# SCH_Record-wav_2025-12-09.net
KiCad netlist of a schematic drawn in EasyEDA
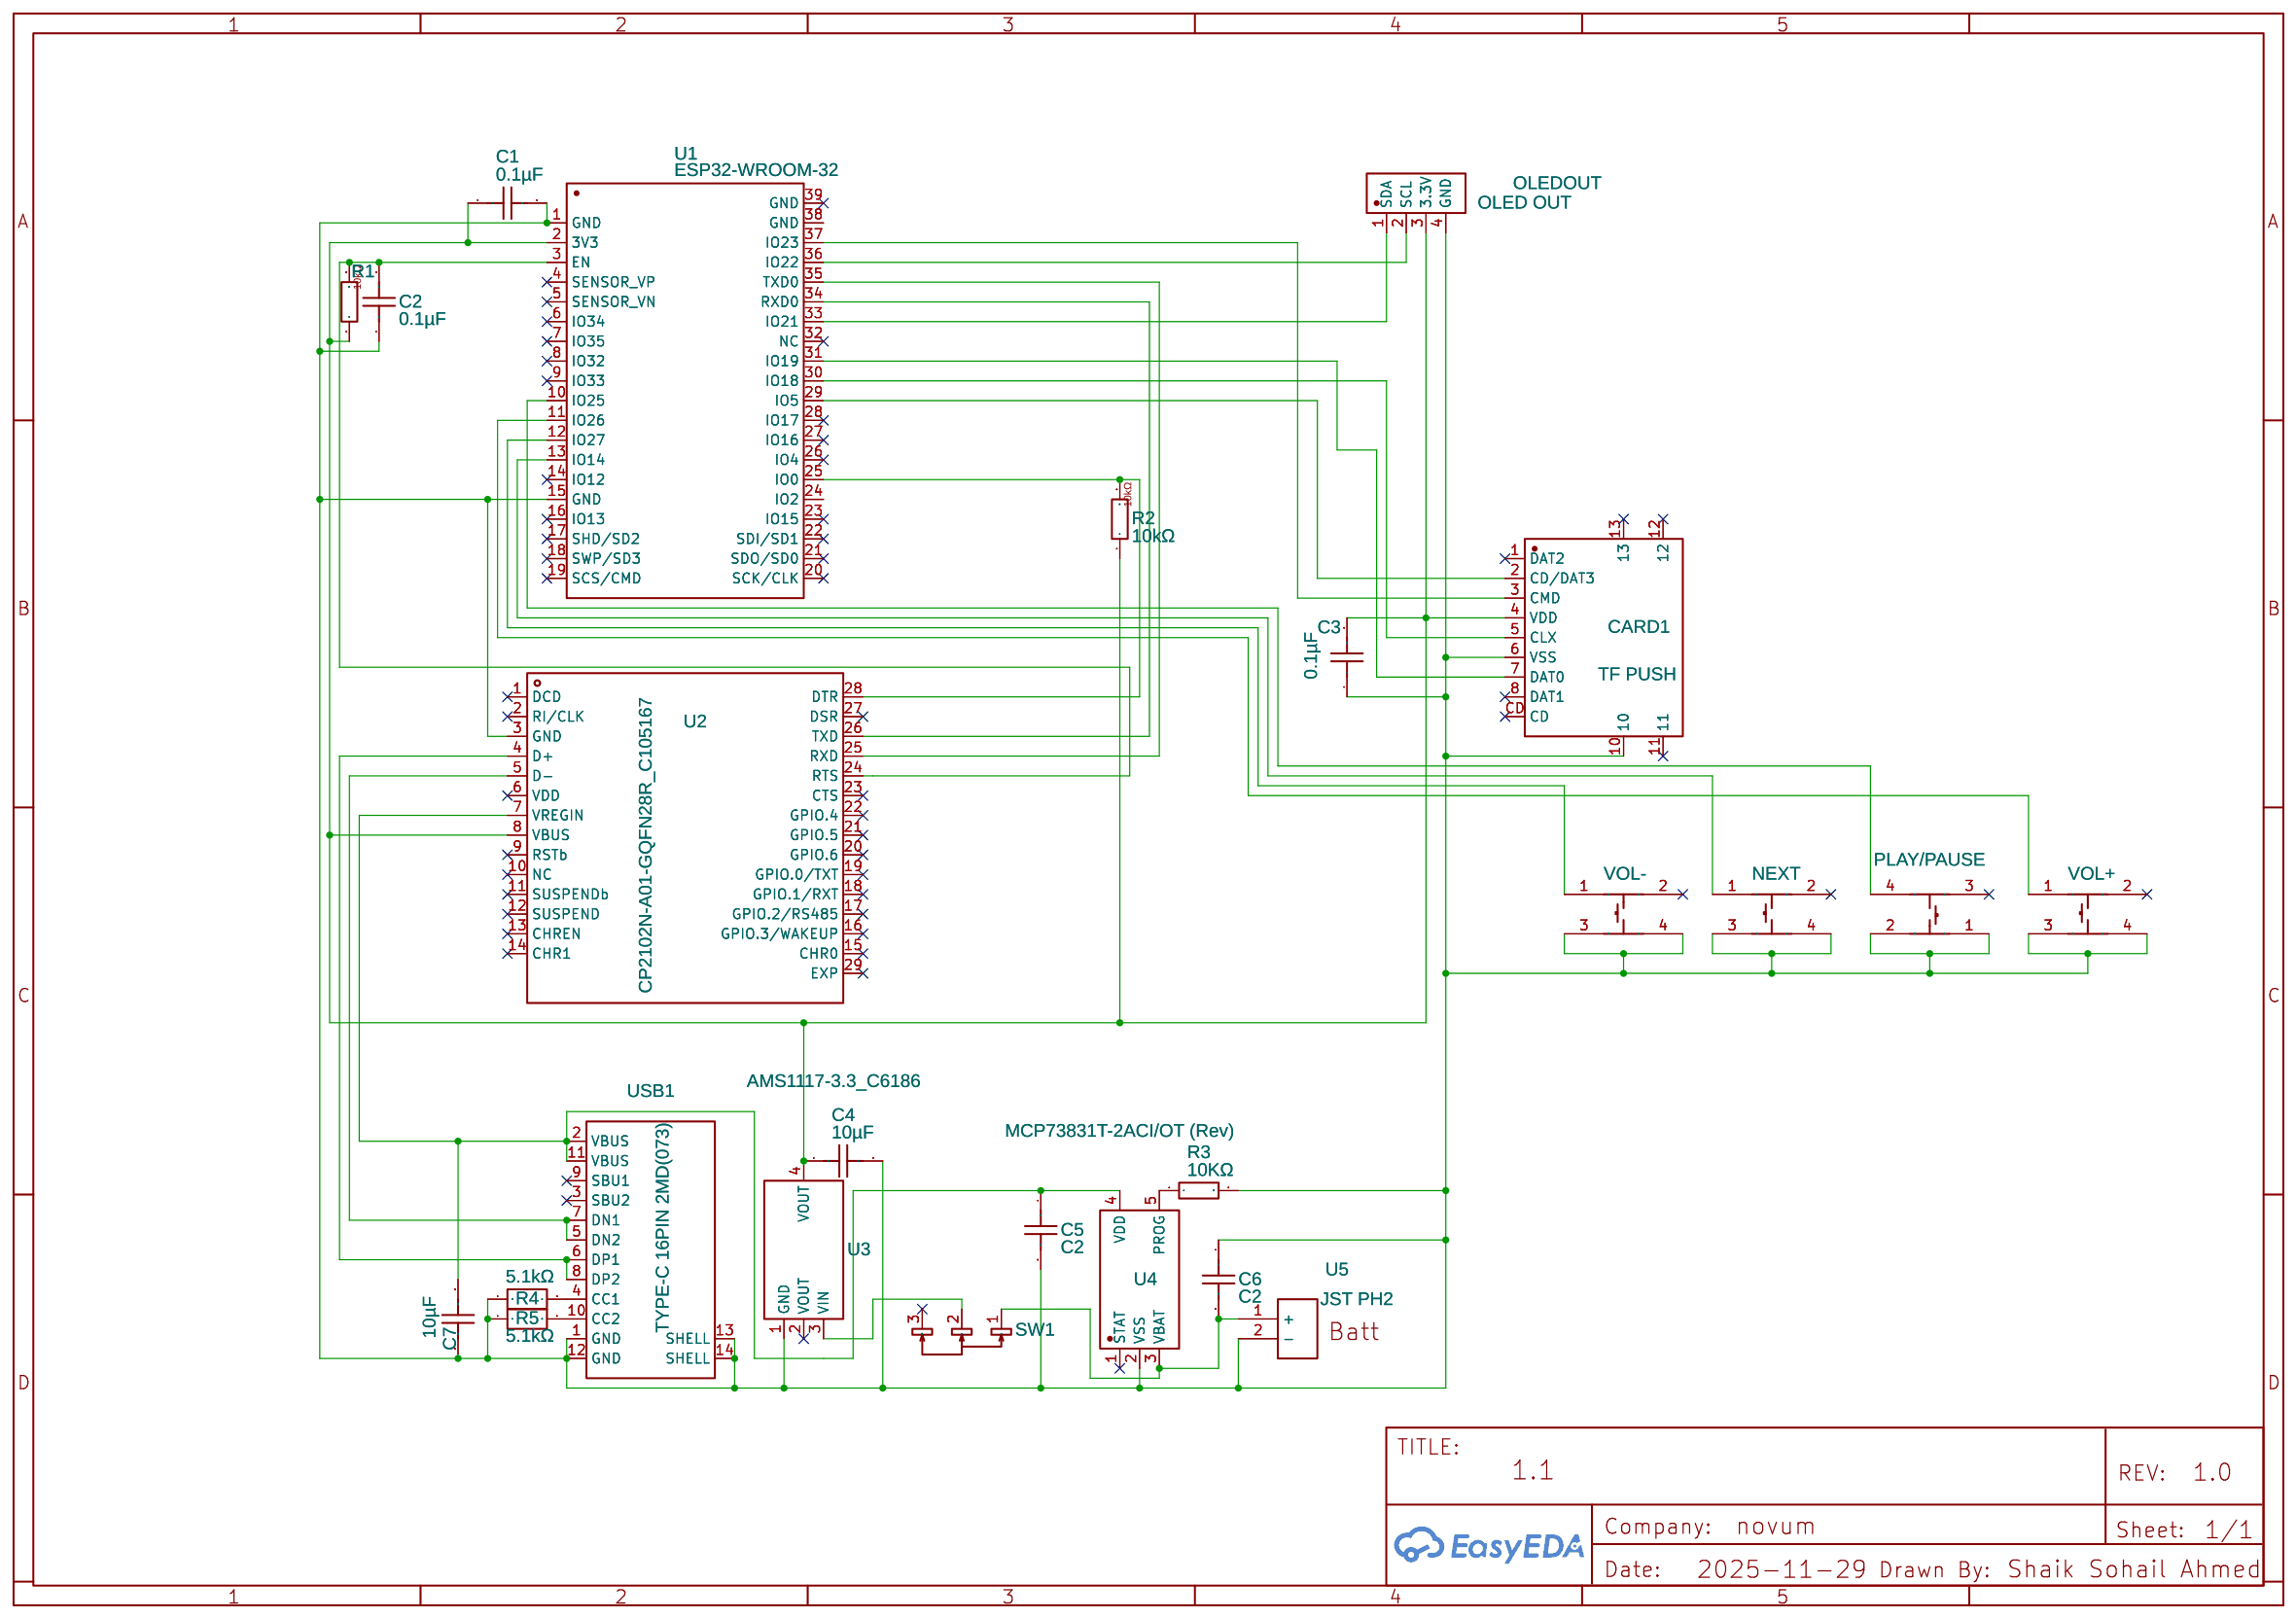
[diagram p0: Sheet_1]
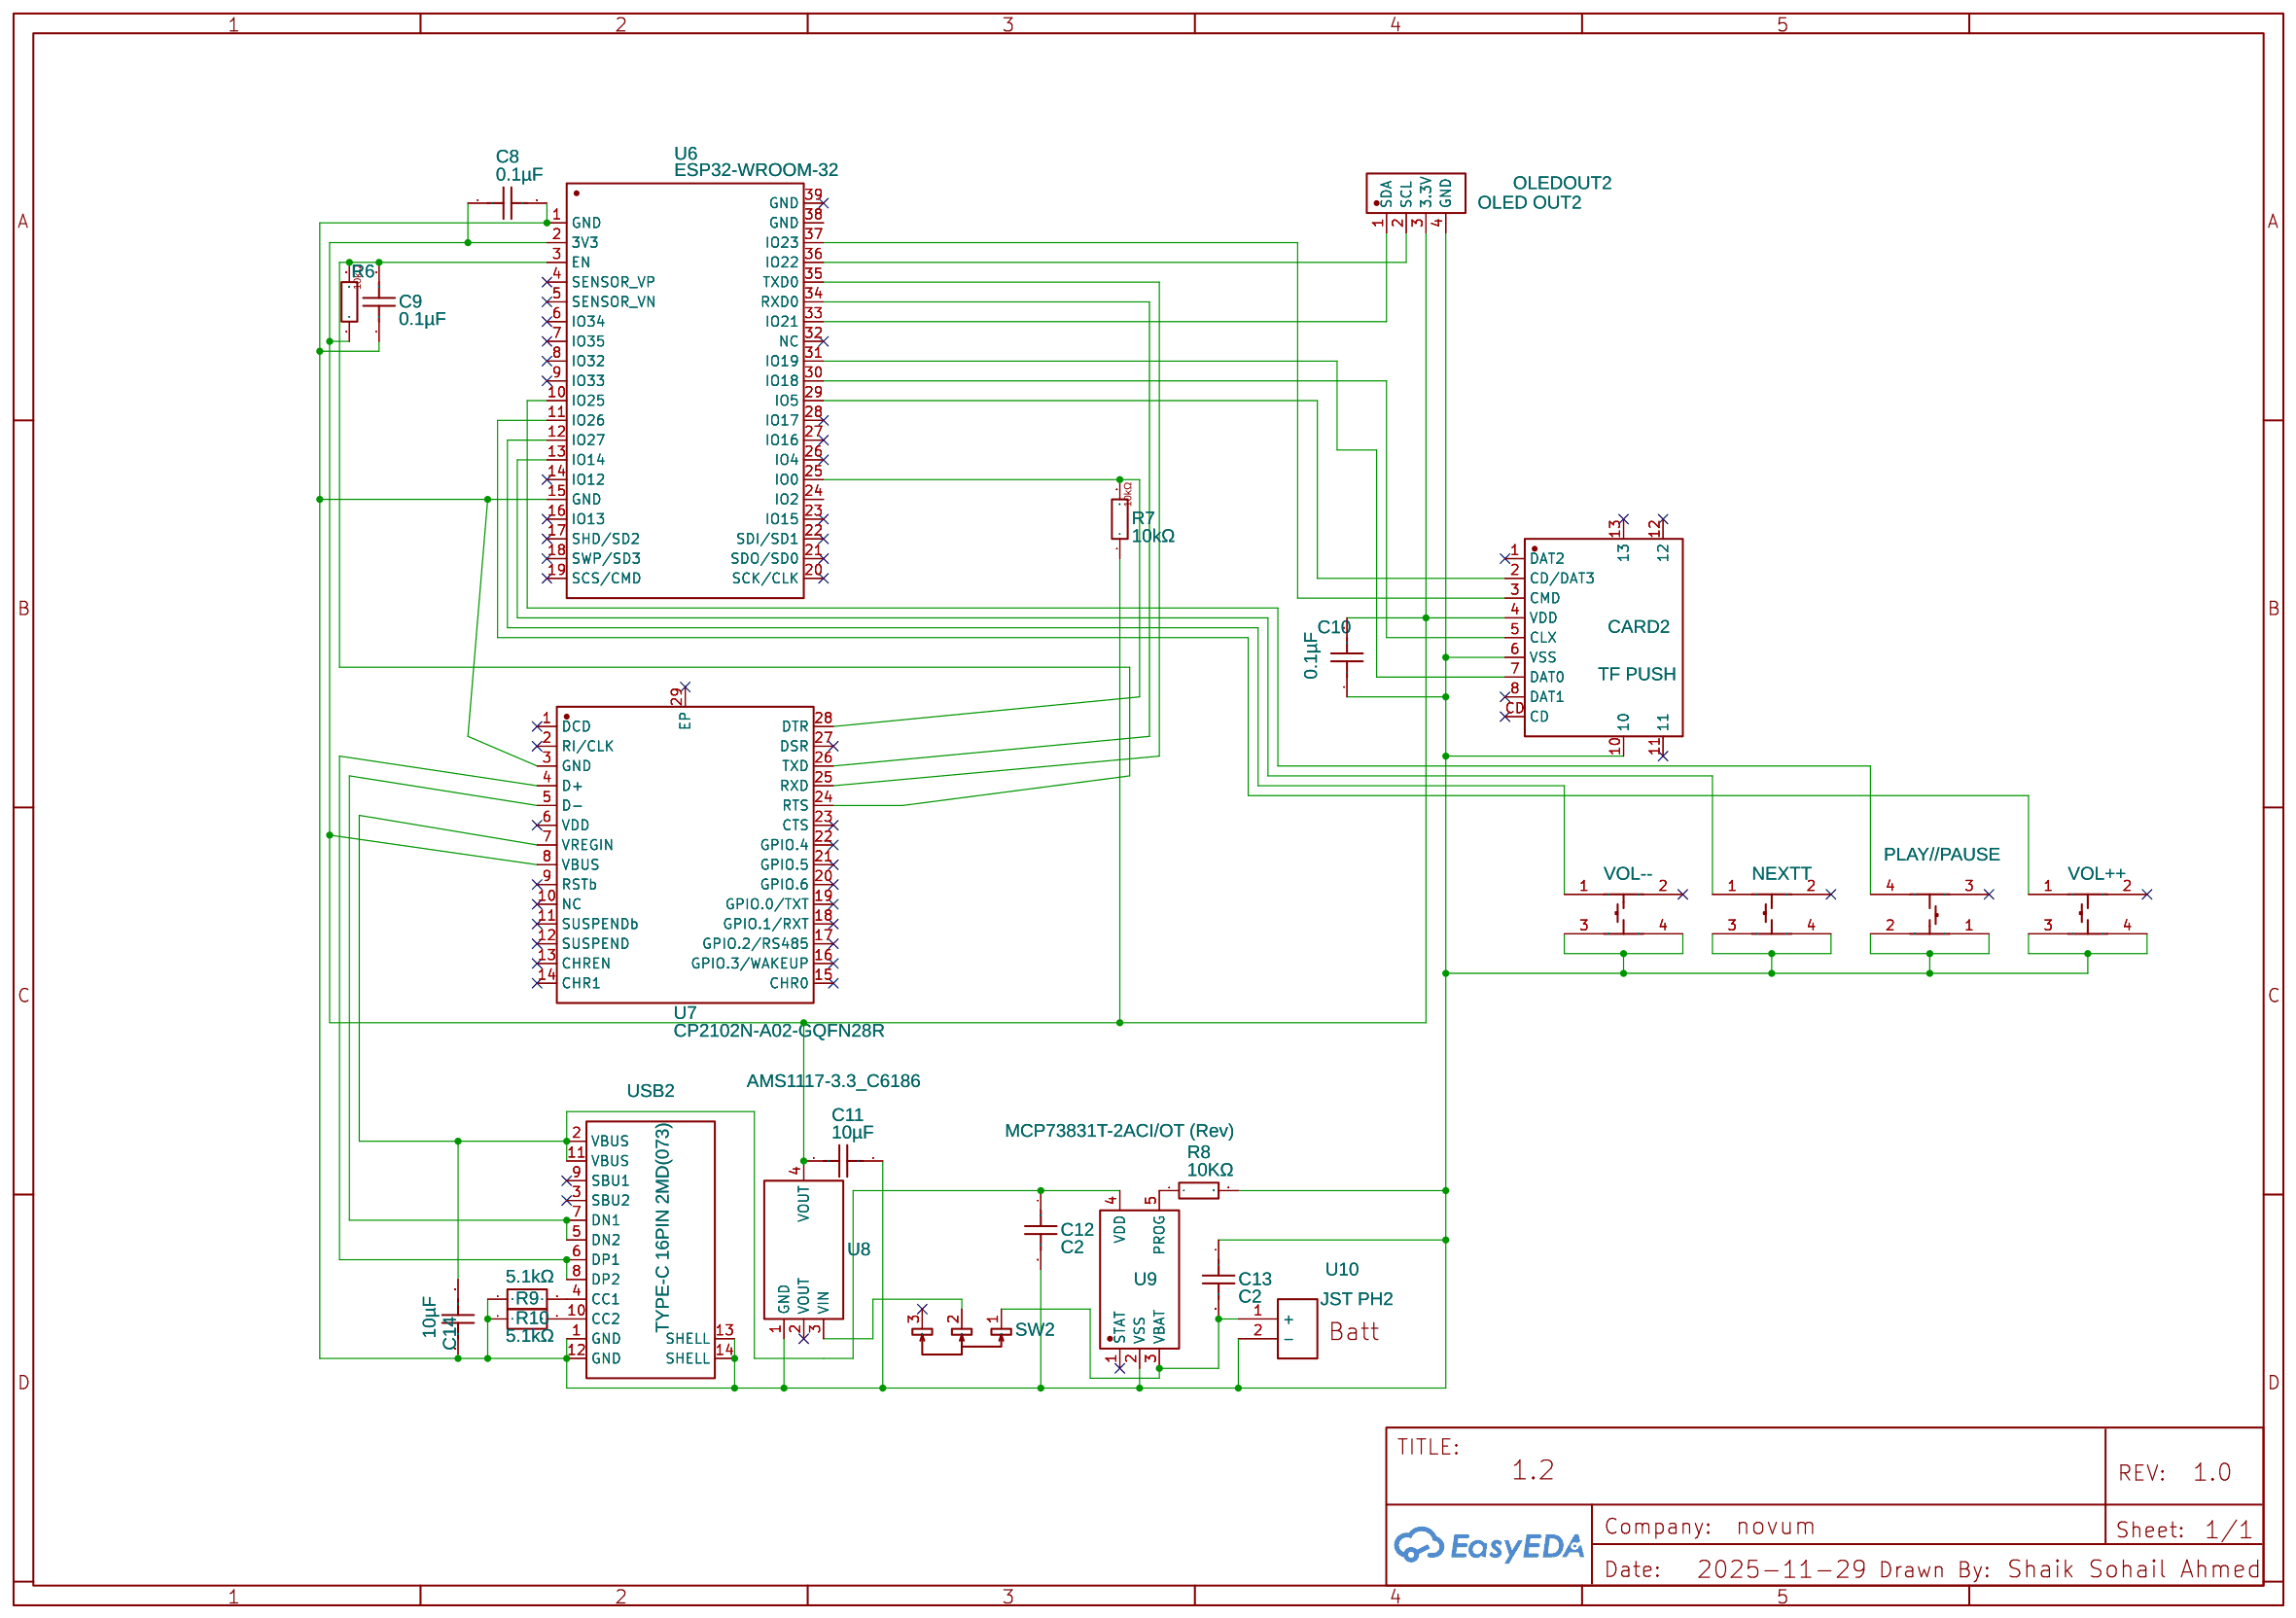
[diagram p1: Sheet_2]

(export (version "E")
  (design (tool "Eeschema 10.0.6"))
  (components
    (comp (ref "C1")
      (value "0.1µF")
      (fields (field (name "Manufacturer Part") "GRM152R60J104ME19D") (field (name "Manufacturer") "muRata"))
      (libsource (lib "") (part "0.1µF_1"))
    )
    (comp (ref "C2")
      (value "0.1µF")
      (fields (field (name "Manufacturer Part") "GRM152R60J104ME19D") (field (name "Manufacturer") "muRata"))
      (libsource (lib "") (part "0.1µF"))
    )
    (comp (ref "C3")
      (value "0.1µF")
      (fields (field (name "Manufacturer Part") "GRM152R60J104ME19D") (field (name "Manufacturer") "muRata"))
      (libsource (lib "") (part "0.1µF"))
    )
    (comp (ref "C4")
      (value "10µF")
      (fields
        (field (name "Manufacturer Part") "CL10A106MA8NRNC")
        (field (name "Manufacturer") "Samsung Electro-Mechanics")
      )
      (libsource (lib "") (part "CL10A106MA8NRNC_1"))
    )
    (comp (ref "C5")
      (value "C2")
      (fields (field (name "Manufacturer Part") "08053C105JAT2A") (field (name "Manufacturer") "KYOCERA AVX"))
      (libsource (lib "") (part "08053C105JAT2A"))
    )
    (comp (ref "C6")
      (value "C2")
      (fields (field (name "Manufacturer Part") "08053C105JAT2A") (field (name "Manufacturer") "KYOCERA AVX"))
      (libsource (lib "") (part "08053C105JAT2A"))
    )
    (comp (ref "C7")
      (value "10µF")
      (fields
        (field (name "Manufacturer Part") "CL10A106MA8NRNC")
        (field (name "Manufacturer") "Samsung Electro-Mechanics")
      )
      (libsource (lib "") (part "CL10A106MA8NRNC"))
    )
    (comp (ref "CARD1")
      (value "TF PUSH")
      (fields (field (name "Manufacturer") "SHOU HAN(首韩)"))
      (libsource (lib "") (part "TF PUSH"))
    )
    (comp (ref "NEXT")
      (value "TS-1002S-07026C")
      (fields (field (name "Manufacturer") "XUNPU(讯普)"))
      (libsource (lib "") (part "TS-1002S-07026C_1"))
    )
    (comp (ref "OLEDOUT") (value "OLED OUT") (libsource (lib "") (part "Solder_Pad_4")))
    (comp (ref "PLAY/PAUSE")
      (value "TS-1002S-07026C")
      (fields (field (name "Manufacturer") "XUNPU(讯普)"))
      (libsource (lib "") (part "TS-1002S-07026C"))
    )
    (comp (ref "R1") (value "10kΩ") (libsource (lib "") (part "10kΩ")))
    (comp (ref "R2") (value "10kΩ") (libsource (lib "") (part "10kΩ")))
    (comp (ref "R3")
      (value "10KΩ")
      (fields (field (name "Manufacturer Part") "CFR0W4J0103A50") (field (name "Manufacturer") "UniOhm"))
      (libsource (lib "") (part "10KΩ"))
    )
    (comp (ref "R4")
      (value "5.1kΩ")
      (fields (field (name "Manufacturer Part") "FRC1206F5101TS") (field (name "Manufacturer") "FOJAN(富捷)"))
      (libsource (lib "") (part "5.1KΩ 1/4W ±1% SMD"))
    )
    (comp (ref "R5")
      (value "5.1kΩ")
      (fields (field (name "Manufacturer Part") "FRC1206F5101TS") (field (name "Manufacturer") "FOJAN(富捷)"))
      (libsource (lib "") (part "5.1KΩ 1/4W ±1% SMD"))
    )
    (comp (ref "SW1")
      (value "MST-12D18G4 SPDT SLIDE SWITCH")
      (fields
        (field (name "Manufacturer Part") "MST-12D18G4 SPDT Slide Switch")
        (field (name "Manufacturer") "SHOU HAN(首韩)")
      )
      (libsource (lib "") (part "MST-12D18G4 SPDT SLIDE SWITCH"))
    )
    (comp (ref "U1")
      (value "ESP32-WROOM-32")
      (fields
        (field (name "Manufacturer Part") "ESP32-WROOM-32-N4")
        (field (name "Manufacturer") "ESPRESSIF(乐鑫)")
      )
      (libsource (lib "") (part "ESP32-WROOM-32"))
    )
    (comp (ref "U2")
      (value "CP2102N-A01-GQFN28R_C105167")
      (fields
        (field (name "Manufacturer Part") "CP2102N-A01-GQFN28R")
        (field (name "Manufacturer") "SKYWORKS/SILICON LABS(芯科)")
      )
      (libsource (lib "") (part "CP2102N-A01-GQFN28R_C105167"))
    )
    (comp (ref "U3")
      (value "AMS1117-3.3_C6186")
      (fields (field (name "Manufacturer Part") "AMS1117-3.3") (field (name "Manufacturer") "AMS"))
      (libsource (lib "") (part "AMS1117-3.3_C6186"))
    )
    (comp (ref "U4")
      (value "MCP73831T-2ACI/OT (Rev)")
      (fields
        (field (name "Manufacturer Part") "MCP73831T-2ACI/OT")
        (field (name "Manufacturer") "MICROCHIP(美国微芯)")
      )
      (libsource (lib "") (part "MCP73831T-2ACI/OT (Rev)"))
    )
    (comp (ref "U5") (value "JST PH2") (libsource (lib "") (part "JST PH2")))
    (comp (ref "USB1")
      (value "TYPE-C 16PIN 2MD(073)")
      (fields (field (name "Manufacturer") "SHOU HAN(首韩)"))
      (libsource (lib "") (part "TYPE-C 16PIN 2MD(073)"))
    )
    (comp (ref "VOL+")
      (value "TS-1002S-07026C")
      (fields (field (name "Manufacturer") "XUNPU(讯普)"))
      (libsource (lib "") (part "TS-1002S-07026C_2"))
    )
    (comp (ref "VOL-")
      (value "TS-1002S-07026C")
      (fields (field (name "Manufacturer") "XUNPU(讯普)"))
      (libsource (lib "") (part "TS-1002S-07026C_3"))
    )
    (comp (ref "C8")
      (value "0.1µF")
      (fields (field (name "Manufacturer Part") "GRM152R60J104ME19D") (field (name "Manufacturer") "muRata"))
      (libsource (lib "") (part "0.1µF_1"))
    )
    (comp (ref "C9")
      (value "0.1µF")
      (fields (field (name "Manufacturer Part") "GRM152R60J104ME19D") (field (name "Manufacturer") "muRata"))
      (libsource (lib "") (part "0.1µF"))
    )
    (comp (ref "C10")
      (value "0.1µF")
      (fields (field (name "Manufacturer Part") "GRM152R60J104ME19D") (field (name "Manufacturer") "muRata"))
      (libsource (lib "") (part "0.1µF"))
    )
    (comp (ref "C11")
      (value "10µF")
      (fields
        (field (name "Manufacturer Part") "CL10A106MA8NRNC")
        (field (name "Manufacturer") "Samsung Electro-Mechanics")
      )
      (libsource (lib "") (part "CL10A106MA8NRNC_1"))
    )
    (comp (ref "C12")
      (value "C2")
      (fields (field (name "Manufacturer Part") "08053C105JAT2A") (field (name "Manufacturer") "KYOCERA AVX"))
      (libsource (lib "") (part "08053C105JAT2A"))
    )
    (comp (ref "C13")
      (value "C2")
      (fields (field (name "Manufacturer Part") "08053C105JAT2A") (field (name "Manufacturer") "KYOCERA AVX"))
      (libsource (lib "") (part "08053C105JAT2A"))
    )
    (comp (ref "C14")
      (value "10µF")
      (fields
        (field (name "Manufacturer Part") "CL10A106MA8NRNC")
        (field (name "Manufacturer") "Samsung Electro-Mechanics")
      )
      (libsource (lib "") (part "CL10A106MA8NRNC"))
    )
    (comp (ref "CARD2")
      (value "TF PUSH")
      (fields (field (name "Manufacturer") "SHOU HAN(首韩)"))
      (libsource (lib "") (part "TF PUSH"))
    )
    (comp (ref "NEXTT")
      (value "TS-1002S-07026C")
      (fields (field (name "Manufacturer") "XUNPU(讯普)"))
      (libsource (lib "") (part "TS-1002S-07026C_3"))
    )
    (comp (ref "OLEDOUT2") (value "OLED OUT2") (libsource (lib "") (part "Solder_Pad_4")))
    (comp (ref "PLAY//PAUSE")
      (value "TS-1002S-07026C")
      (fields (field (name "Manufacturer") "XUNPU(讯普)"))
      (libsource (lib "") (part "TS-1002S-07026C_1"))
    )
    (comp (ref "R6") (value "10kΩ") (libsource (lib "") (part "10kΩ")))
    (comp (ref "R7") (value "10kΩ") (libsource (lib "") (part "10kΩ")))
    (comp (ref "R8")
      (value "10KΩ")
      (fields (field (name "Manufacturer Part") "CFR0W4J0103A50") (field (name "Manufacturer") "UniOhm"))
      (libsource (lib "") (part "10KΩ"))
    )
    (comp (ref "R9")
      (value "5.1kΩ")
      (fields (field (name "Manufacturer Part") "FRC1206F5101TS") (field (name "Manufacturer") "FOJAN(富捷)"))
      (libsource (lib "") (part "5.1KΩ 1/4W ±1% SMD"))
    )
    (comp (ref "R10")
      (value "5.1kΩ")
      (fields (field (name "Manufacturer Part") "FRC1206F5101TS") (field (name "Manufacturer") "FOJAN(富捷)"))
      (libsource (lib "") (part "5.1KΩ 1/4W ±1% SMD"))
    )
    (comp (ref "SW2")
      (value "MST-12D18G4 SPDT SLIDE SWITCH")
      (fields
        (field (name "Manufacturer Part") "MST-12D18G4 SPDT Slide Switch")
        (field (name "Manufacturer") "SHOU HAN(首韩)")
      )
      (libsource (lib "") (part "MST-12D18G4 SPDT SLIDE SWITCH"))
    )
    (comp (ref "U6")
      (value "ESP32-WROOM-32")
      (fields
        (field (name "Manufacturer Part") "ESP32-WROOM-32-N4")
        (field (name "Manufacturer") "ESPRESSIF(乐鑫)")
      )
      (libsource (lib "") (part "ESP32-WROOM-32"))
    )
    (comp (ref "U7")
      (value "CP2102N-A02-GQFN28R")
      (fields (field (name "Manufacturer") "SKYWORKS/SILICON LABS(芯科)"))
      (libsource (lib "") (part "CP2102N-A02-GQFN28R"))
    )
    (comp (ref "U8")
      (value "AMS1117-3.3_C6186")
      (fields (field (name "Manufacturer Part") "AMS1117-3.3") (field (name "Manufacturer") "AMS"))
      (libsource (lib "") (part "AMS1117-3.3_C6186"))
    )
    (comp (ref "U9")
      (value "MCP73831T-2ACI/OT (Rev)")
      (fields
        (field (name "Manufacturer Part") "MCP73831T-2ACI/OT")
        (field (name "Manufacturer") "MICROCHIP(美国微芯)")
      )
      (libsource (lib "") (part "MCP73831T-2ACI/OT (Rev)"))
    )
    (comp (ref "U10") (value "JST PH2") (libsource (lib "") (part "JST PH2")))
    (comp (ref "USB2")
      (value "TYPE-C 16PIN 2MD(073)")
      (fields (field (name "Manufacturer") "SHOU HAN(首韩)"))
      (libsource (lib "") (part "TYPE-C 16PIN 2MD(073)"))
    )
    (comp (ref "VOL++")
      (value "TS-1002S-07026C")
      (fields (field (name "Manufacturer") "XUNPU(讯普)"))
      (libsource (lib "") (part "TS-1002S-07026C_2"))
    )
    (comp (ref "VOL--")
      (value "TS-1002S-07026C")
      (fields (field (name "Manufacturer") "XUNPU(讯普)"))
      (libsource (lib "") (part "TS-1002S-07026C"))
    )
  )
  (nets
    (net (code "1") (name "Net-(CARD1-CD{slash}DAT3)") (class "Default")
      (node (ref "CARD1") (pin "2") (pinfunction "CD/DAT3_2") (pintype "unspecified"))
      (node (ref "U1") (pin "29") (pinfunction "IO5_29") (pintype "unspecified"))
    )
    (net (code "2") (name "Net-(CARD1-CLX)") (class "Default")
      (node (ref "CARD1") (pin "5") (pinfunction "CLX_5") (pintype "unspecified"))
      (node (ref "U1") (pin "30") (pinfunction "IO18_30") (pintype "unspecified"))
    )
    (net (code "3") (name "Net-(CARD1-CMD)") (class "Default")
      (node (ref "CARD1") (pin "3") (pinfunction "CMD_3") (pintype "unspecified"))
      (node (ref "U1") (pin "37") (pinfunction "IO23_37") (pintype "unspecified"))
    )
    (net (code "4") (name "Net-(CARD1-DAT0)") (class "Default")
      (node (ref "CARD1") (pin "7") (pinfunction "DAT0_7") (pintype "unspecified"))
      (node (ref "U1") (pin "31") (pinfunction "IO19_31") (pintype "unspecified"))
    )
    (net (code "5") (name "Net-(CARD1-VDD)") (class "Default")
      (node (ref "C1") (pin "1") (pinfunction "1_1") (pintype "unspecified"))
      (node (ref "C3") (pin "2") (pinfunction "2_2") (pintype "unspecified"))
      (node (ref "C4") (pin "1") (pinfunction "1_1") (pintype "unspecified"))
      (node (ref "CARD1") (pin "4") (pinfunction "VDD_4") (pintype "unspecified"))
      (node (ref "OLEDOUT") (pin "3") (pinfunction "3.3V_3") (pintype "unspecified"))
      (node (ref "R1") (pin "1") (pinfunction "1_1") (pintype "unspecified"))
      (node (ref "R2") (pin "1") (pinfunction "1_1") (pintype "unspecified"))
      (node (ref "U1") (pin "2") (pinfunction "3V3_2") (pintype "unspecified"))
      (node (ref "U2") (pin "8") (pinfunction "VBUS_8") (pintype "unspecified"))
      (node (ref "U3") (pin "4") (pinfunction "VOUT_4") (pintype "unspecified"))
    )
    (net (code "6") (name "Net-(CARD1-VSS)") (class "Default")
      (node (ref "C1") (pin "2") (pinfunction "2_2") (pintype "unspecified"))
      (node (ref "C2") (pin "1") (pinfunction "1_1") (pintype "unspecified"))
      (node (ref "C3") (pin "1") (pinfunction "1_1") (pintype "unspecified"))
      (node (ref "C4") (pin "2") (pinfunction "2_2") (pintype "unspecified"))
      (node (ref "C5") (pin "2") (pinfunction "2_2") (pintype "unspecified"))
      (node (ref "C6") (pin "1") (pinfunction "1_1") (pintype "unspecified"))
      (node (ref "C7") (pin "2") (pinfunction "2_2") (pintype "unspecified"))
      (node (ref "CARD1") (pin "10") (pinfunction "10_10") (pintype "unspecified"))
      (node (ref "CARD1") (pin "6") (pinfunction "VSS_6") (pintype "unspecified"))
      (node (ref "NEXT") (pin "3") (pinfunction "3_3") (pintype "unspecified"))
      (node (ref "NEXT") (pin "4") (pinfunction "4_4") (pintype "unspecified"))
      (node (ref "OLEDOUT") (pin "4") (pinfunction "GND_4") (pintype "unspecified"))
      (node (ref "PLAY/PAUSE") (pin "1") (pinfunction "1_1") (pintype "unspecified"))
      (node (ref "PLAY/PAUSE") (pin "2") (pinfunction "2_2") (pintype "unspecified"))
      (node (ref "R3") (pin "2") (pinfunction "2_2") (pintype "input"))
      (node (ref "R4") (pin "1") (pinfunction "1_1") (pintype "unspecified"))
      (node (ref "R5") (pin "1") (pinfunction "1_1") (pintype "unspecified"))
      (node (ref "U1") (pin "1") (pinfunction "GND_1") (pintype "unspecified"))
      (node (ref "U1") (pin "15") (pinfunction "GND_15") (pintype "unspecified"))
      (node (ref "U2") (pin "3") (pinfunction "GND_3") (pintype "unspecified"))
      (node (ref "U3") (pin "1") (pinfunction "GND_1") (pintype "unspecified"))
      (node (ref "U4") (pin "2") (pinfunction "VSS_2") (pintype "unspecified"))
      (node (ref "U5") (pin "2") (pinfunction "-_2") (pintype "unspecified"))
      (node (ref "USB1") (pin "1") (pinfunction "GND_1") (pintype "unspecified"))
      (node (ref "USB1") (pin "12") (pinfunction "GND_12") (pintype "unspecified"))
      (node (ref "USB1") (pin "13") (pinfunction "SHELL_13") (pintype "unspecified"))
      (node (ref "USB1") (pin "14") (pinfunction "SHELL_14") (pintype "unspecified"))
      (node (ref "VOL+") (pin "3") (pinfunction "3_3") (pintype "unspecified"))
      (node (ref "VOL+") (pin "4") (pinfunction "4_4") (pintype "unspecified"))
      (node (ref "VOL-") (pin "3") (pinfunction "3_3") (pintype "unspecified"))
      (node (ref "VOL-") (pin "4") (pinfunction "4_4") (pintype "unspecified"))
    )
    (net (code "7") (name "Net-(CARD2-CD{slash}DAT3)") (class "Default")
      (node (ref "CARD2") (pin "2") (pinfunction "CD/DAT3_2") (pintype "unspecified"))
      (node (ref "U6") (pin "29") (pinfunction "IO5_29") (pintype "unspecified"))
    )
    (net (code "8") (name "Net-(CARD2-CLX)") (class "Default")
      (node (ref "CARD2") (pin "5") (pinfunction "CLX_5") (pintype "unspecified"))
      (node (ref "U6") (pin "30") (pinfunction "IO18_30") (pintype "unspecified"))
    )
    (net (code "9") (name "Net-(CARD2-CMD)") (class "Default")
      (node (ref "CARD2") (pin "3") (pinfunction "CMD_3") (pintype "unspecified"))
      (node (ref "U6") (pin "37") (pinfunction "IO23_37") (pintype "unspecified"))
    )
    (net (code "10") (name "Net-(CARD2-DAT0)") (class "Default")
      (node (ref "CARD2") (pin "7") (pinfunction "DAT0_7") (pintype "unspecified"))
      (node (ref "U6") (pin "31") (pinfunction "IO19_31") (pintype "unspecified"))
    )
    (net (code "11") (name "Net-(CARD2-VDD)") (class "Default")
      (node (ref "C10") (pin "2") (pinfunction "2_2") (pintype "unspecified"))
      (node (ref "C11") (pin "1") (pinfunction "1_1") (pintype "unspecified"))
      (node (ref "C8") (pin "1") (pinfunction "1_1") (pintype "unspecified"))
      (node (ref "CARD2") (pin "4") (pinfunction "VDD_4") (pintype "unspecified"))
      (node (ref "OLEDOUT2") (pin "3") (pinfunction "3.3V_3") (pintype "unspecified"))
      (node (ref "R6") (pin "1") (pinfunction "1_1") (pintype "unspecified"))
      (node (ref "R7") (pin "1") (pinfunction "1_1") (pintype "unspecified"))
      (node (ref "U6") (pin "2") (pinfunction "3V3_2") (pintype "unspecified"))
      (node (ref "U7") (pin "8") (pinfunction "VBUS_8") (pintype "unspecified"))
      (node (ref "U8") (pin "4") (pinfunction "VOUT_4") (pintype "unspecified"))
    )
    (net (code "12") (name "Net-(CARD2-VSS)") (class "Default")
      (node (ref "C10") (pin "1") (pinfunction "1_1") (pintype "unspecified"))
      (node (ref "C11") (pin "2") (pinfunction "2_2") (pintype "unspecified"))
      (node (ref "C12") (pin "2") (pinfunction "2_2") (pintype "unspecified"))
      (node (ref "C13") (pin "1") (pinfunction "1_1") (pintype "unspecified"))
      (node (ref "C14") (pin "2") (pinfunction "2_2") (pintype "unspecified"))
      (node (ref "C8") (pin "2") (pinfunction "2_2") (pintype "unspecified"))
      (node (ref "C9") (pin "1") (pinfunction "1_1") (pintype "unspecified"))
      (node (ref "CARD2") (pin "10") (pinfunction "10_10") (pintype "unspecified"))
      (node (ref "CARD2") (pin "6") (pinfunction "VSS_6") (pintype "unspecified"))
      (node (ref "NEXTT") (pin "3") (pinfunction "3_3") (pintype "unspecified"))
      (node (ref "NEXTT") (pin "4") (pinfunction "4_4") (pintype "unspecified"))
      (node (ref "OLEDOUT2") (pin "4") (pinfunction "GND_4") (pintype "unspecified"))
      (node (ref "PLAY//PAUSE") (pin "1") (pinfunction "1_1") (pintype "unspecified"))
      (node (ref "PLAY//PAUSE") (pin "2") (pinfunction "2_2") (pintype "unspecified"))
      (node (ref "R10") (pin "1") (pinfunction "1_1") (pintype "unspecified"))
      (node (ref "R8") (pin "2") (pinfunction "2_2") (pintype "input"))
      (node (ref "R9") (pin "1") (pinfunction "1_1") (pintype "unspecified"))
      (node (ref "U10") (pin "2") (pinfunction "-_2") (pintype "unspecified"))
      (node (ref "U6") (pin "1") (pinfunction "GND_1") (pintype "unspecified"))
      (node (ref "U6") (pin "15") (pinfunction "GND_15") (pintype "unspecified"))
      (node (ref "U7") (pin "3") (pinfunction "GND_3") (pintype "unspecified"))
      (node (ref "U8") (pin "1") (pinfunction "GND_1") (pintype "unspecified"))
      (node (ref "U9") (pin "2") (pinfunction "VSS_2") (pintype "unspecified"))
      (node (ref "USB2") (pin "1") (pinfunction "GND_1") (pintype "unspecified"))
      (node (ref "USB2") (pin "12") (pinfunction "GND_12") (pintype "unspecified"))
      (node (ref "USB2") (pin "13") (pinfunction "SHELL_13") (pintype "unspecified"))
      (node (ref "USB2") (pin "14") (pinfunction "SHELL_14") (pintype "unspecified"))
      (node (ref "VOL++") (pin "3") (pinfunction "3_3") (pintype "unspecified"))
      (node (ref "VOL++") (pin "4") (pinfunction "4_4") (pintype "unspecified"))
      (node (ref "VOL--") (pin "3") (pinfunction "3_3") (pintype "unspecified"))
      (node (ref "VOL--") (pin "4") (pinfunction "4_4") (pintype "unspecified"))
    )
    (net (code "13") (name "Net-(OLEDOUT-SCL)") (class "Default")
      (node (ref "OLEDOUT") (pin "2") (pinfunction "SCL_2") (pintype "unspecified"))
      (node (ref "U1") (pin "36") (pinfunction "IO22_36") (pintype "unspecified"))
    )
    (net (code "14") (name "Net-(OLEDOUT-SDA)") (class "Default")
      (node (ref "OLEDOUT") (pin "1") (pinfunction "SDA_1") (pintype "unspecified"))
      (node (ref "U1") (pin "33") (pinfunction "IO21_33") (pintype "unspecified"))
    )
    (net (code "15") (name "Net-(OLEDOUT2-SCL)") (class "Default")
      (node (ref "OLEDOUT2") (pin "2") (pinfunction "SCL_2") (pintype "unspecified"))
      (node (ref "U6") (pin "36") (pinfunction "IO22_36") (pintype "unspecified"))
    )
    (net (code "16") (name "Net-(OLEDOUT2-SDA)") (class "Default")
      (node (ref "OLEDOUT2") (pin "1") (pinfunction "SDA_1") (pintype "unspecified"))
      (node (ref "U6") (pin "33") (pinfunction "IO21_33") (pintype "unspecified"))
    )
    (net (code "17") (name "Net-(U1-EN)") (class "Default")
      (node (ref "C2") (pin "2") (pinfunction "2_2") (pintype "unspecified"))
      (node (ref "R1") (pin "2") (pinfunction "2_2") (pintype "unspecified"))
      (node (ref "U1") (pin "3") (pinfunction "EN_3") (pintype "unspecified"))
      (node (ref "U2") (pin "24") (pinfunction "RTS_24") (pintype "unspecified"))
    )
    (net (code "18") (name "Net-(U1-IO0)") (class "Default")
      (node (ref "R2") (pin "2") (pinfunction "2_2") (pintype "unspecified"))
      (node (ref "U1") (pin "25") (pinfunction "IO0_25") (pintype "unspecified"))
      (node (ref "U2") (pin "28") (pinfunction "DTR_28") (pintype "unspecified"))
    )
    (net (code "19") (name "Net-(U1-IO14)") (class "Default")
      (node (ref "NEXT") (pin "1") (pinfunction "1_1") (pintype "unspecified"))
      (node (ref "U1") (pin "13") (pinfunction "IO14_13") (pintype "unspecified"))
    )
    (net (code "20") (name "Net-(U1-IO25)") (class "Default")
      (node (ref "PLAY/PAUSE") (pin "4") (pinfunction "4_4") (pintype "unspecified"))
      (node (ref "U1") (pin "10") (pinfunction "IO25_10") (pintype "unspecified"))
    )
    (net (code "21") (name "Net-(U1-IO26)") (class "Default")
      (node (ref "U1") (pin "11") (pinfunction "IO26_11") (pintype "unspecified"))
      (node (ref "VOL+") (pin "1") (pinfunction "1_1") (pintype "unspecified"))
    )
    (net (code "22") (name "Net-(U1-IO27)") (class "Default")
      (node (ref "U1") (pin "12") (pinfunction "IO27_12") (pintype "unspecified"))
      (node (ref "VOL-") (pin "1") (pinfunction "1_1") (pintype "unspecified"))
    )
    (net (code "23") (name "Net-(U1-RXD0)") (class "Default")
      (node (ref "U1") (pin "34") (pinfunction "RXD0_34") (pintype "unspecified"))
      (node (ref "U2") (pin "26") (pinfunction "TXD_26") (pintype "unspecified"))
    )
    (net (code "24") (name "Net-(U1-TXD0)") (class "Default")
      (node (ref "U1") (pin "35") (pinfunction "TXD0_35") (pintype "unspecified"))
      (node (ref "U2") (pin "25") (pinfunction "RXD_25") (pintype "unspecified"))
    )
    (net (code "25") (name "Net-(U2-D+)") (class "Default")
      (node (ref "U2") (pin "4") (pinfunction "D+_4") (pintype "unspecified"))
      (node (ref "USB1") (pin "6") (pinfunction "DP1_6") (pintype "unspecified"))
      (node (ref "USB1") (pin "8") (pinfunction "DP2_8") (pintype "unspecified"))
    )
    (net (code "26") (name "Net-(U2-D-)") (class "Default")
      (node (ref "U2") (pin "5") (pinfunction "D-_5") (pintype "unspecified"))
      (node (ref "USB1") (pin "5") (pinfunction "DN2_5") (pintype "unspecified"))
      (node (ref "USB1") (pin "7") (pinfunction "DN1_7") (pintype "unspecified"))
    )
    (net (code "27") (name "Net-(U2-VREGIN)") (class "Default")
      (node (ref "C5") (pin "1") (pinfunction "1_1") (pintype "unspecified"))
      (node (ref "C7") (pin "1") (pinfunction "1_1") (pintype "unspecified"))
      (node (ref "U2") (pin "7") (pinfunction "VREGIN_7") (pintype "unspecified"))
      (node (ref "U4") (pin "4") (pinfunction "VDD_4") (pintype "unspecified"))
      (node (ref "USB1") (pin "11") (pinfunction "VBUS_11") (pintype "unspecified"))
      (node (ref "USB1") (pin "2") (pinfunction "VBUS_2") (pintype "unspecified"))
    )
    (net (code "28") (name "Net-(U3-VIN)") (class "Default")
      (node (ref "SW1") (pin "2") (pinfunction "2_2") (pintype "unspecified"))
      (node (ref "U3") (pin "3") (pinfunction "VIN_3") (pintype "unspecified"))
    )
    (net (code "29") (name "Net-(U4-PROG)") (class "Default")
      (node (ref "R3") (pin "1") (pinfunction "1_1") (pintype "input"))
      (node (ref "U4") (pin "5") (pinfunction "PROG_5") (pintype "unspecified"))
    )
    (net (code "30") (name "Net-(U4-VBAT)") (class "Default")
      (node (ref "C6") (pin "2") (pinfunction "2_2") (pintype "unspecified"))
      (node (ref "SW1") (pin "1") (pinfunction "1_1") (pintype "unspecified"))
      (node (ref "U4") (pin "3") (pinfunction "VBAT_3") (pintype "unspecified"))
      (node (ref "U5") (pin "1") (pinfunction "+_1") (pintype "unspecified"))
    )
    (net (code "31") (name "Net-(U6-EN)") (class "Default")
      (node (ref "C9") (pin "2") (pinfunction "2_2") (pintype "unspecified"))
      (node (ref "R6") (pin "2") (pinfunction "2_2") (pintype "unspecified"))
      (node (ref "U6") (pin "3") (pinfunction "EN_3") (pintype "unspecified"))
      (node (ref "U7") (pin "24") (pinfunction "RTS_24") (pintype "unspecified"))
    )
    (net (code "32") (name "Net-(U6-IO0)") (class "Default")
      (node (ref "R7") (pin "2") (pinfunction "2_2") (pintype "unspecified"))
      (node (ref "U6") (pin "25") (pinfunction "IO0_25") (pintype "unspecified"))
      (node (ref "U7") (pin "28") (pinfunction "DTR_28") (pintype "unspecified"))
    )
    (net (code "33") (name "Net-(U6-IO14)") (class "Default")
      (node (ref "NEXTT") (pin "1") (pinfunction "1_1") (pintype "unspecified"))
      (node (ref "U6") (pin "13") (pinfunction "IO14_13") (pintype "unspecified"))
    )
    (net (code "34") (name "Net-(U6-IO25)") (class "Default")
      (node (ref "PLAY//PAUSE") (pin "4") (pinfunction "4_4") (pintype "unspecified"))
      (node (ref "U6") (pin "10") (pinfunction "IO25_10") (pintype "unspecified"))
    )
    (net (code "35") (name "Net-(U6-IO26)") (class "Default")
      (node (ref "U6") (pin "11") (pinfunction "IO26_11") (pintype "unspecified"))
      (node (ref "VOL++") (pin "1") (pinfunction "1_1") (pintype "unspecified"))
    )
    (net (code "36") (name "Net-(U6-IO27)") (class "Default")
      (node (ref "U6") (pin "12") (pinfunction "IO27_12") (pintype "unspecified"))
      (node (ref "VOL--") (pin "1") (pinfunction "1_1") (pintype "unspecified"))
    )
    (net (code "37") (name "Net-(U6-RXD0)") (class "Default")
      (node (ref "U6") (pin "34") (pinfunction "RXD0_34") (pintype "unspecified"))
      (node (ref "U7") (pin "26") (pinfunction "TXD_26") (pintype "unspecified"))
    )
    (net (code "38") (name "Net-(U6-TXD0)") (class "Default")
      (node (ref "U6") (pin "35") (pinfunction "TXD0_35") (pintype "unspecified"))
      (node (ref "U7") (pin "25") (pinfunction "RXD_25") (pintype "unspecified"))
    )
    (net (code "39") (name "Net-(U7-D+)") (class "Default")
      (node (ref "U7") (pin "4") (pinfunction "D+_4") (pintype "unspecified"))
      (node (ref "USB2") (pin "6") (pinfunction "DP1_6") (pintype "unspecified"))
      (node (ref "USB2") (pin "8") (pinfunction "DP2_8") (pintype "unspecified"))
    )
    (net (code "40") (name "Net-(U7-D-)") (class "Default")
      (node (ref "U7") (pin "5") (pinfunction "D-_5") (pintype "unspecified"))
      (node (ref "USB2") (pin "5") (pinfunction "DN2_5") (pintype "unspecified"))
      (node (ref "USB2") (pin "7") (pinfunction "DN1_7") (pintype "unspecified"))
    )
    (net (code "41") (name "Net-(U7-VREGIN)") (class "Default")
      (node (ref "C12") (pin "1") (pinfunction "1_1") (pintype "unspecified"))
      (node (ref "C14") (pin "1") (pinfunction "1_1") (pintype "unspecified"))
      (node (ref "U7") (pin "7") (pinfunction "VREGIN_7") (pintype "unspecified"))
      (node (ref "U9") (pin "4") (pinfunction "VDD_4") (pintype "unspecified"))
      (node (ref "USB2") (pin "11") (pinfunction "VBUS_11") (pintype "unspecified"))
      (node (ref "USB2") (pin "2") (pinfunction "VBUS_2") (pintype "unspecified"))
    )
    (net (code "42") (name "Net-(U8-VIN)") (class "Default")
      (node (ref "SW2") (pin "2") (pinfunction "2_2") (pintype "unspecified"))
      (node (ref "U8") (pin "3") (pinfunction "VIN_3") (pintype "unspecified"))
    )
    (net (code "43") (name "Net-(U9-PROG)") (class "Default")
      (node (ref "R8") (pin "1") (pinfunction "1_1") (pintype "input"))
      (node (ref "U9") (pin "5") (pinfunction "PROG_5") (pintype "unspecified"))
    )
    (net (code "44") (name "Net-(U10-+)") (class "Default")
      (node (ref "C13") (pin "2") (pinfunction "2_2") (pintype "unspecified"))
      (node (ref "SW2") (pin "1") (pinfunction "1_1") (pintype "unspecified"))
      (node (ref "U10") (pin "1") (pinfunction "+_1") (pintype "unspecified"))
      (node (ref "U9") (pin "3") (pinfunction "VBAT_3") (pintype "unspecified"))
    )
    (net (code "45") (name "Net-(USB1-CC1)") (class "Default")
      (node (ref "R4") (pin "2") (pinfunction "2_2") (pintype "unspecified"))
      (node (ref "USB1") (pin "4") (pinfunction "CC1_4") (pintype "unspecified"))
    )
    (net (code "46") (name "Net-(USB1-CC2)") (class "Default")
      (node (ref "R5") (pin "2") (pinfunction "2_2") (pintype "unspecified"))
      (node (ref "USB1") (pin "10") (pinfunction "CC2_10") (pintype "unspecified"))
    )
    (net (code "47") (name "Net-(USB2-CC1)") (class "Default")
      (node (ref "R9") (pin "2") (pinfunction "2_2") (pintype "unspecified"))
      (node (ref "USB2") (pin "4") (pinfunction "CC1_4") (pintype "unspecified"))
    )
    (net (code "48") (name "Net-(USB2-CC2)") (class "Default")
      (node (ref "R10") (pin "2") (pinfunction "2_2") (pintype "unspecified"))
      (node (ref "USB2") (pin "10") (pinfunction "CC2_10") (pintype "unspecified"))
    )
    (net (code "49") (name "unconnected-(CARD1-DAT1-Pad8)") (class "Default")
      (node (ref "CARD1") (pin "8") (pinfunction "DAT1_8") (pintype "unspecified+no_connect"))
    )
    (net (code "50") (name "unconnected-(CARD1-DAT2-Pad1)") (class "Default")
      (node (ref "CARD1") (pin "1") (pinfunction "DAT2_1") (pintype "unspecified+no_connect"))
    )
    (net (code "51") (name "unconnected-(CARD1-Pad11)") (class "Default")
      (node (ref "CARD1") (pin "11") (pinfunction "11_11") (pintype "unspecified+no_connect"))
    )
    (net (code "52") (name "unconnected-(CARD1-Pad12)") (class "Default")
      (node (ref "CARD1") (pin "12") (pinfunction "12_12") (pintype "unspecified+no_connect"))
    )
    (net (code "53") (name "unconnected-(CARD1-Pad13)") (class "Default")
      (node (ref "CARD1") (pin "13") (pinfunction "13_13") (pintype "unspecified+no_connect"))
    )
    (net (code "54") (name "unconnected-(CARD1-PadCD)") (class "Default")
      (node (ref "CARD1") (pin "CD") (pinfunction "CD_CD") (pintype "unspecified+no_connect"))
    )
    (net (code "55") (name "unconnected-(CARD2-DAT1-Pad8)") (class "Default")
      (node (ref "CARD2") (pin "8") (pinfunction "DAT1_8") (pintype "unspecified+no_connect"))
    )
    (net (code "56") (name "unconnected-(CARD2-DAT2-Pad1)") (class "Default")
      (node (ref "CARD2") (pin "1") (pinfunction "DAT2_1") (pintype "unspecified+no_connect"))
    )
    (net (code "57") (name "unconnected-(CARD2-Pad11)") (class "Default")
      (node (ref "CARD2") (pin "11") (pinfunction "11_11") (pintype "unspecified+no_connect"))
    )
    (net (code "58") (name "unconnected-(CARD2-Pad12)") (class "Default")
      (node (ref "CARD2") (pin "12") (pinfunction "12_12") (pintype "unspecified+no_connect"))
    )
    (net (code "59") (name "unconnected-(CARD2-Pad13)") (class "Default")
      (node (ref "CARD2") (pin "13") (pinfunction "13_13") (pintype "unspecified+no_connect"))
    )
    (net (code "60") (name "unconnected-(CARD2-PadCD)") (class "Default")
      (node (ref "CARD2") (pin "CD") (pinfunction "CD_CD") (pintype "unspecified+no_connect"))
    )
    (net (code "61") (name "unconnected-(NEXT-Pad2)") (class "Default")
      (node (ref "NEXT") (pin "2") (pinfunction "2_2") (pintype "unspecified+no_connect"))
    )
    (net (code "62") (name "unconnected-(NEXTT-Pad2)") (class "Default")
      (node (ref "NEXTT") (pin "2") (pinfunction "2_2") (pintype "unspecified+no_connect"))
    )
    (net (code "63") (name "unconnected-(PLAY//PAUSE-Pad3)") (class "Default")
      (node (ref "PLAY//PAUSE") (pin "3") (pinfunction "3_3") (pintype "unspecified+no_connect"))
    )
    (net (code "64") (name "unconnected-(PLAY/PAUSE-Pad3)") (class "Default")
      (node (ref "PLAY/PAUSE") (pin "3") (pinfunction "3_3") (pintype "unspecified+no_connect"))
    )
    (net (code "65") (name "unconnected-(SW1-Pad3)") (class "Default")
      (node (ref "SW1") (pin "3") (pinfunction "3_3") (pintype "unspecified+no_connect"))
    )
    (net (code "66") (name "unconnected-(SW2-Pad3)") (class "Default")
      (node (ref "SW2") (pin "3") (pinfunction "3_3") (pintype "unspecified+no_connect"))
    )
    (net (code "67") (name "unconnected-(U1-GND-Pad38)") (class "Default")
      (node (ref "U1") (pin "38") (pinfunction "GND_38") (pintype "unspecified"))
    )
    (net (code "68") (name "unconnected-(U1-GND-Pad39)") (class "Default")
      (node (ref "U1") (pin "39") (pinfunction "GND_39") (pintype "unspecified+no_connect"))
    )
    (net (code "69") (name "unconnected-(U1-IO2-Pad24)") (class "Default")
      (node (ref "U1") (pin "24") (pinfunction "IO2_24") (pintype "unspecified"))
    )
    (net (code "70") (name "unconnected-(U1-IO4-Pad26)") (class "Default")
      (node (ref "U1") (pin "26") (pinfunction "IO4_26") (pintype "unspecified+no_connect"))
    )
    (net (code "71") (name "unconnected-(U1-IO12-Pad14)") (class "Default")
      (node (ref "U1") (pin "14") (pinfunction "IO12_14") (pintype "unspecified+no_connect"))
    )
    (net (code "72") (name "unconnected-(U1-IO13-Pad16)") (class "Default")
      (node (ref "U1") (pin "16") (pinfunction "IO13_16") (pintype "unspecified+no_connect"))
    )
    (net (code "73") (name "unconnected-(U1-IO15-Pad23)") (class "Default")
      (node (ref "U1") (pin "23") (pinfunction "IO15_23") (pintype "unspecified+no_connect"))
    )
    (net (code "74") (name "unconnected-(U1-IO16-Pad27)") (class "Default")
      (node (ref "U1") (pin "27") (pinfunction "IO16_27") (pintype "unspecified+no_connect"))
    )
    (net (code "75") (name "unconnected-(U1-IO17-Pad28)") (class "Default")
      (node (ref "U1") (pin "28") (pinfunction "IO17_28") (pintype "unspecified+no_connect"))
    )
    (net (code "76") (name "unconnected-(U1-IO32-Pad8)") (class "Default")
      (node (ref "U1") (pin "8") (pinfunction "IO32_8") (pintype "unspecified+no_connect"))
    )
    (net (code "77") (name "unconnected-(U1-IO33-Pad9)") (class "Default")
      (node (ref "U1") (pin "9") (pinfunction "IO33_9") (pintype "unspecified+no_connect"))
    )
    (net (code "78") (name "unconnected-(U1-IO34-Pad6)") (class "Default")
      (node (ref "U1") (pin "6") (pinfunction "IO34_6") (pintype "unspecified+no_connect"))
    )
    (net (code "79") (name "unconnected-(U1-IO35-Pad7)") (class "Default")
      (node (ref "U1") (pin "7") (pinfunction "IO35_7") (pintype "unspecified+no_connect"))
    )
    (net (code "80") (name "unconnected-(U1-NC-Pad32)") (class "Default")
      (node (ref "U1") (pin "32") (pinfunction "NC_32") (pintype "unspecified+no_connect"))
    )
    (net (code "81") (name "unconnected-(U1-SCK{slash}CLK-Pad20)") (class "Default")
      (node (ref "U1") (pin "20") (pinfunction "SCK/CLK_20") (pintype "unspecified+no_connect"))
    )
    (net (code "82") (name "unconnected-(U1-SCS{slash}CMD-Pad19)") (class "Default")
      (node (ref "U1") (pin "19") (pinfunction "SCS/CMD_19") (pintype "unspecified+no_connect"))
    )
    (net (code "83") (name "unconnected-(U1-SDI{slash}SD1-Pad22)") (class "Default")
      (node (ref "U1") (pin "22") (pinfunction "SDI/SD1_22") (pintype "unspecified+no_connect"))
    )
    (net (code "84") (name "unconnected-(U1-SDO{slash}SD0-Pad21)") (class "Default")
      (node (ref "U1") (pin "21") (pinfunction "SDO/SD0_21") (pintype "unspecified+no_connect"))
    )
    (net (code "85") (name "unconnected-(U1-SENSOR_VN-Pad5)") (class "Default")
      (node (ref "U1") (pin "5") (pinfunction "SENSOR_VN_5") (pintype "unspecified+no_connect"))
    )
    (net (code "86") (name "unconnected-(U1-SENSOR_VP-Pad4)") (class "Default")
      (node (ref "U1") (pin "4") (pinfunction "SENSOR_VP_4") (pintype "unspecified+no_connect"))
    )
    (net (code "87") (name "unconnected-(U1-SHD{slash}SD2-Pad17)") (class "Default")
      (node (ref "U1") (pin "17") (pinfunction "SHD/SD2_17") (pintype "unspecified+no_connect"))
    )
    (net (code "88") (name "unconnected-(U1-SWP{slash}SD3-Pad18)") (class "Default")
      (node (ref "U1") (pin "18") (pinfunction "SWP/SD3_18") (pintype "unspecified+no_connect"))
    )
    (net (code "89") (name "unconnected-(U2-CHR0-Pad15)") (class "Default")
      (node (ref "U2") (pin "15") (pinfunction "CHR0_15") (pintype "unspecified+no_connect"))
    )
    (net (code "90") (name "unconnected-(U2-CHR1-Pad14)") (class "Default")
      (node (ref "U2") (pin "14") (pinfunction "CHR1_14") (pintype "unspecified+no_connect"))
    )
    (net (code "91") (name "unconnected-(U2-CHREN-Pad13)") (class "Default")
      (node (ref "U2") (pin "13") (pinfunction "CHREN_13") (pintype "unspecified+no_connect"))
    )
    (net (code "92") (name "unconnected-(U2-CTS-Pad23)") (class "Default")
      (node (ref "U2") (pin "23") (pinfunction "CTS_23") (pintype "unspecified+no_connect"))
    )
    (net (code "93") (name "unconnected-(U2-DCD-Pad1)") (class "Default")
      (node (ref "U2") (pin "1") (pinfunction "DCD_1") (pintype "unspecified+no_connect"))
    )
    (net (code "94") (name "unconnected-(U2-DSR-Pad27)") (class "Default")
      (node (ref "U2") (pin "27") (pinfunction "DSR_27") (pintype "unspecified+no_connect"))
    )
    (net (code "95") (name "unconnected-(U2-EXP-Pad29)") (class "Default")
      (node (ref "U2") (pin "29") (pinfunction "EXP_29") (pintype "unspecified+no_connect"))
    )
    (net (code "96") (name "unconnected-(U2-GPIO.0{slash}TXT-Pad19)") (class "Default")
      (node (ref "U2") (pin "19") (pinfunction "GPIO.0/TXT_19") (pintype "unspecified+no_connect"))
    )
    (net (code "97") (name "unconnected-(U2-GPIO.1{slash}RXT-Pad18)") (class "Default")
      (node (ref "U2") (pin "18") (pinfunction "GPIO.1/RXT_18") (pintype "unspecified+no_connect"))
    )
    (net (code "98") (name "unconnected-(U2-GPIO.2{slash}RS485-Pad17)") (class "Default")
      (node (ref "U2") (pin "17") (pinfunction "GPIO.2/RS485_17") (pintype "unspecified+no_connect"))
    )
    (net (code "99") (name "unconnected-(U2-GPIO.3{slash}WAKEUP-Pad16)") (class "Default")
      (node (ref "U2") (pin "16") (pinfunction "GPIO.3/WAKEUP_16") (pintype "unspecified+no_connect"))
    )
    (net (code "100") (name "unconnected-(U2-GPIO.4-Pad22)") (class "Default")
      (node (ref "U2") (pin "22") (pinfunction "GPIO.4_22") (pintype "unspecified+no_connect"))
    )
    (net (code "101") (name "unconnected-(U2-GPIO.5-Pad21)") (class "Default")
      (node (ref "U2") (pin "21") (pinfunction "GPIO.5_21") (pintype "unspecified+no_connect"))
    )
    (net (code "102") (name "unconnected-(U2-GPIO.6-Pad20)") (class "Default")
      (node (ref "U2") (pin "20") (pinfunction "GPIO.6_20") (pintype "unspecified+no_connect"))
    )
    (net (code "103") (name "unconnected-(U2-NC-Pad10)") (class "Default")
      (node (ref "U2") (pin "10") (pinfunction "NC_10") (pintype "unspecified+no_connect"))
    )
    (net (code "104") (name "unconnected-(U2-RI{slash}CLK-Pad2)") (class "Default")
      (node (ref "U2") (pin "2") (pinfunction "RI/CLK_2") (pintype "unspecified+no_connect"))
    )
    (net (code "105") (name "unconnected-(U2-RSTb-Pad9)") (class "Default")
      (node (ref "U2") (pin "9") (pinfunction "RSTb_9") (pintype "unspecified+no_connect"))
    )
    (net (code "106") (name "unconnected-(U2-SUSPEND-Pad12)") (class "Default")
      (node (ref "U2") (pin "12") (pinfunction "SUSPEND_12") (pintype "unspecified+no_connect"))
    )
    (net (code "107") (name "unconnected-(U2-SUSPENDb-Pad11)") (class "Default")
      (node (ref "U2") (pin "11") (pinfunction "SUSPENDb_11") (pintype "unspecified+no_connect"))
    )
    (net (code "108") (name "unconnected-(U2-VDD-Pad6)") (class "Default")
      (node (ref "U2") (pin "6") (pinfunction "VDD_6") (pintype "unspecified+no_connect"))
    )
    (net (code "109") (name "unconnected-(U3-VOUT-Pad2)") (class "Default")
      (node (ref "U3") (pin "2") (pinfunction "VOUT_2") (pintype "unspecified+no_connect"))
    )
    (net (code "110") (name "unconnected-(U4-STAT-Pad1)") (class "Default")
      (node (ref "U4") (pin "1") (pinfunction "STAT_1") (pintype "unspecified+no_connect"))
    )
    (net (code "111") (name "unconnected-(U6-GND-Pad38)") (class "Default")
      (node (ref "U6") (pin "38") (pinfunction "GND_38") (pintype "unspecified"))
    )
    (net (code "112") (name "unconnected-(U6-GND-Pad39)") (class "Default")
      (node (ref "U6") (pin "39") (pinfunction "GND_39") (pintype "unspecified+no_connect"))
    )
    (net (code "113") (name "unconnected-(U6-IO2-Pad24)") (class "Default")
      (node (ref "U6") (pin "24") (pinfunction "IO2_24") (pintype "unspecified"))
    )
    (net (code "114") (name "unconnected-(U6-IO4-Pad26)") (class "Default")
      (node (ref "U6") (pin "26") (pinfunction "IO4_26") (pintype "unspecified+no_connect"))
    )
    (net (code "115") (name "unconnected-(U6-IO12-Pad14)") (class "Default")
      (node (ref "U6") (pin "14") (pinfunction "IO12_14") (pintype "unspecified+no_connect"))
    )
    (net (code "116") (name "unconnected-(U6-IO13-Pad16)") (class "Default")
      (node (ref "U6") (pin "16") (pinfunction "IO13_16") (pintype "unspecified+no_connect"))
    )
    (net (code "117") (name "unconnected-(U6-IO15-Pad23)") (class "Default")
      (node (ref "U6") (pin "23") (pinfunction "IO15_23") (pintype "unspecified+no_connect"))
    )
    (net (code "118") (name "unconnected-(U6-IO16-Pad27)") (class "Default")
      (node (ref "U6") (pin "27") (pinfunction "IO16_27") (pintype "unspecified+no_connect"))
    )
    (net (code "119") (name "unconnected-(U6-IO17-Pad28)") (class "Default")
      (node (ref "U6") (pin "28") (pinfunction "IO17_28") (pintype "unspecified+no_connect"))
    )
    (net (code "120") (name "unconnected-(U6-IO32-Pad8)") (class "Default")
      (node (ref "U6") (pin "8") (pinfunction "IO32_8") (pintype "unspecified+no_connect"))
    )
    (net (code "121") (name "unconnected-(U6-IO33-Pad9)") (class "Default")
      (node (ref "U6") (pin "9") (pinfunction "IO33_9") (pintype "unspecified+no_connect"))
    )
    (net (code "122") (name "unconnected-(U6-IO34-Pad6)") (class "Default")
      (node (ref "U6") (pin "6") (pinfunction "IO34_6") (pintype "unspecified+no_connect"))
    )
    (net (code "123") (name "unconnected-(U6-IO35-Pad7)") (class "Default")
      (node (ref "U6") (pin "7") (pinfunction "IO35_7") (pintype "unspecified+no_connect"))
    )
    (net (code "124") (name "unconnected-(U6-NC-Pad32)") (class "Default")
      (node (ref "U6") (pin "32") (pinfunction "NC_32") (pintype "unspecified+no_connect"))
    )
    (net (code "125") (name "unconnected-(U6-SCK{slash}CLK-Pad20)") (class "Default")
      (node (ref "U6") (pin "20") (pinfunction "SCK/CLK_20") (pintype "unspecified+no_connect"))
    )
    (net (code "126") (name "unconnected-(U6-SCS{slash}CMD-Pad19)") (class "Default")
      (node (ref "U6") (pin "19") (pinfunction "SCS/CMD_19") (pintype "unspecified+no_connect"))
    )
    (net (code "127") (name "unconnected-(U6-SDI{slash}SD1-Pad22)") (class "Default")
      (node (ref "U6") (pin "22") (pinfunction "SDI/SD1_22") (pintype "unspecified+no_connect"))
    )
    (net (code "128") (name "unconnected-(U6-SDO{slash}SD0-Pad21)") (class "Default")
      (node (ref "U6") (pin "21") (pinfunction "SDO/SD0_21") (pintype "unspecified+no_connect"))
    )
    (net (code "129") (name "unconnected-(U6-SENSOR_VN-Pad5)") (class "Default")
      (node (ref "U6") (pin "5") (pinfunction "SENSOR_VN_5") (pintype "unspecified+no_connect"))
    )
    (net (code "130") (name "unconnected-(U6-SENSOR_VP-Pad4)") (class "Default")
      (node (ref "U6") (pin "4") (pinfunction "SENSOR_VP_4") (pintype "unspecified+no_connect"))
    )
    (net (code "131") (name "unconnected-(U6-SHD{slash}SD2-Pad17)") (class "Default")
      (node (ref "U6") (pin "17") (pinfunction "SHD/SD2_17") (pintype "unspecified+no_connect"))
    )
    (net (code "132") (name "unconnected-(U6-SWP{slash}SD3-Pad18)") (class "Default")
      (node (ref "U6") (pin "18") (pinfunction "SWP/SD3_18") (pintype "unspecified+no_connect"))
    )
    (net (code "133") (name "unconnected-(U7-CHR0-Pad15)") (class "Default")
      (node (ref "U7") (pin "15") (pinfunction "CHR0_15") (pintype "unspecified+no_connect"))
    )
    (net (code "134") (name "unconnected-(U7-CHR1-Pad14)") (class "Default")
      (node (ref "U7") (pin "14") (pinfunction "CHR1_14") (pintype "unspecified+no_connect"))
    )
    (net (code "135") (name "unconnected-(U7-CHREN-Pad13)") (class "Default")
      (node (ref "U7") (pin "13") (pinfunction "CHREN_13") (pintype "unspecified+no_connect"))
    )
    (net (code "136") (name "unconnected-(U7-CTS-Pad23)") (class "Default")
      (node (ref "U7") (pin "23") (pinfunction "CTS_23") (pintype "unspecified+no_connect"))
    )
    (net (code "137") (name "unconnected-(U7-DCD-Pad1)") (class "Default")
      (node (ref "U7") (pin "1") (pinfunction "DCD_1") (pintype "unspecified+no_connect"))
    )
    (net (code "138") (name "unconnected-(U7-DSR-Pad27)") (class "Default")
      (node (ref "U7") (pin "27") (pinfunction "DSR_27") (pintype "unspecified+no_connect"))
    )
    (net (code "139") (name "unconnected-(U7-EP-Pad29)") (class "Default")
      (node (ref "U7") (pin "29") (pinfunction "EP_29") (pintype "unspecified+no_connect"))
    )
    (net (code "140") (name "unconnected-(U7-GPIO.0{slash}TXT-Pad19)") (class "Default")
      (node (ref "U7") (pin "19") (pinfunction "GPIO.0/TXT_19") (pintype "unspecified+no_connect"))
    )
    (net (code "141") (name "unconnected-(U7-GPIO.1{slash}RXT-Pad18)") (class "Default")
      (node (ref "U7") (pin "18") (pinfunction "GPIO.1/RXT_18") (pintype "unspecified+no_connect"))
    )
    (net (code "142") (name "unconnected-(U7-GPIO.2{slash}RS485-Pad17)") (class "Default")
      (node (ref "U7") (pin "17") (pinfunction "GPIO.2/RS485_17") (pintype "unspecified+no_connect"))
    )
    (net (code "143") (name "unconnected-(U7-GPIO.3{slash}WAKEUP-Pad16)") (class "Default")
      (node (ref "U7") (pin "16") (pinfunction "GPIO.3/WAKEUP_16") (pintype "unspecified+no_connect"))
    )
    (net (code "144") (name "unconnected-(U7-GPIO.4-Pad22)") (class "Default")
      (node (ref "U7") (pin "22") (pinfunction "GPIO.4_22") (pintype "unspecified+no_connect"))
    )
    (net (code "145") (name "unconnected-(U7-GPIO.5-Pad21)") (class "Default")
      (node (ref "U7") (pin "21") (pinfunction "GPIO.5_21") (pintype "unspecified+no_connect"))
    )
    (net (code "146") (name "unconnected-(U7-GPIO.6-Pad20)") (class "Default")
      (node (ref "U7") (pin "20") (pinfunction "GPIO.6_20") (pintype "unspecified+no_connect"))
    )
    (net (code "147") (name "unconnected-(U7-NC-Pad10)") (class "Default")
      (node (ref "U7") (pin "10") (pinfunction "NC_10") (pintype "unspecified+no_connect"))
    )
    (net (code "148") (name "unconnected-(U7-RI{slash}CLK-Pad2)") (class "Default")
      (node (ref "U7") (pin "2") (pinfunction "RI/CLK_2") (pintype "unspecified+no_connect"))
    )
    (net (code "149") (name "unconnected-(U7-RSTb-Pad9)") (class "Default")
      (node (ref "U7") (pin "9") (pinfunction "RSTb_9") (pintype "unspecified+no_connect"))
    )
    (net (code "150") (name "unconnected-(U7-SUSPEND-Pad12)") (class "Default")
      (node (ref "U7") (pin "12") (pinfunction "SUSPEND_12") (pintype "unspecified+no_connect"))
    )
    (net (code "151") (name "unconnected-(U7-SUSPENDb-Pad11)") (class "Default")
      (node (ref "U7") (pin "11") (pinfunction "SUSPENDb_11") (pintype "unspecified+no_connect"))
    )
    (net (code "152") (name "unconnected-(U7-VDD-Pad6)") (class "Default")
      (node (ref "U7") (pin "6") (pinfunction "VDD_6") (pintype "unspecified+no_connect"))
    )
    (net (code "153") (name "unconnected-(U8-VOUT-Pad2)") (class "Default")
      (node (ref "U8") (pin "2") (pinfunction "VOUT_2") (pintype "unspecified+no_connect"))
    )
    (net (code "154") (name "unconnected-(U9-STAT-Pad1)") (class "Default")
      (node (ref "U9") (pin "1") (pinfunction "STAT_1") (pintype "unspecified+no_connect"))
    )
    (net (code "155") (name "unconnected-(USB1-SBU1-Pad9)") (class "Default")
      (node (ref "USB1") (pin "9") (pinfunction "SBU1_9") (pintype "unspecified+no_connect"))
    )
    (net (code "156") (name "unconnected-(USB1-SBU2-Pad3)") (class "Default")
      (node (ref "USB1") (pin "3") (pinfunction "SBU2_3") (pintype "unspecified+no_connect"))
    )
    (net (code "157") (name "unconnected-(USB2-SBU1-Pad9)") (class "Default")
      (node (ref "USB2") (pin "9") (pinfunction "SBU1_9") (pintype "unspecified+no_connect"))
    )
    (net (code "158") (name "unconnected-(USB2-SBU2-Pad3)") (class "Default")
      (node (ref "USB2") (pin "3") (pinfunction "SBU2_3") (pintype "unspecified+no_connect"))
    )
    (net (code "159") (name "unconnected-(VOL++-Pad2)") (class "Default")
      (node (ref "VOL++") (pin "2") (pinfunction "2_2") (pintype "unspecified+no_connect"))
    )
    (net (code "160") (name "unconnected-(VOL+-Pad2)") (class "Default")
      (node (ref "VOL+") (pin "2") (pinfunction "2_2") (pintype "unspecified+no_connect"))
    )
    (net (code "161") (name "unconnected-(VOL---Pad2)") (class "Default")
      (node (ref "VOL--") (pin "2") (pinfunction "2_2") (pintype "unspecified+no_connect"))
    )
    (net (code "162") (name "unconnected-(VOL--Pad2)") (class "Default")
      (node (ref "VOL-") (pin "2") (pinfunction "2_2") (pintype "unspecified+no_connect"))
    )
  )
)
